# SMD_Latch_Switch_v01.net
KiCad netlist of a schematic drawn in EAGLE
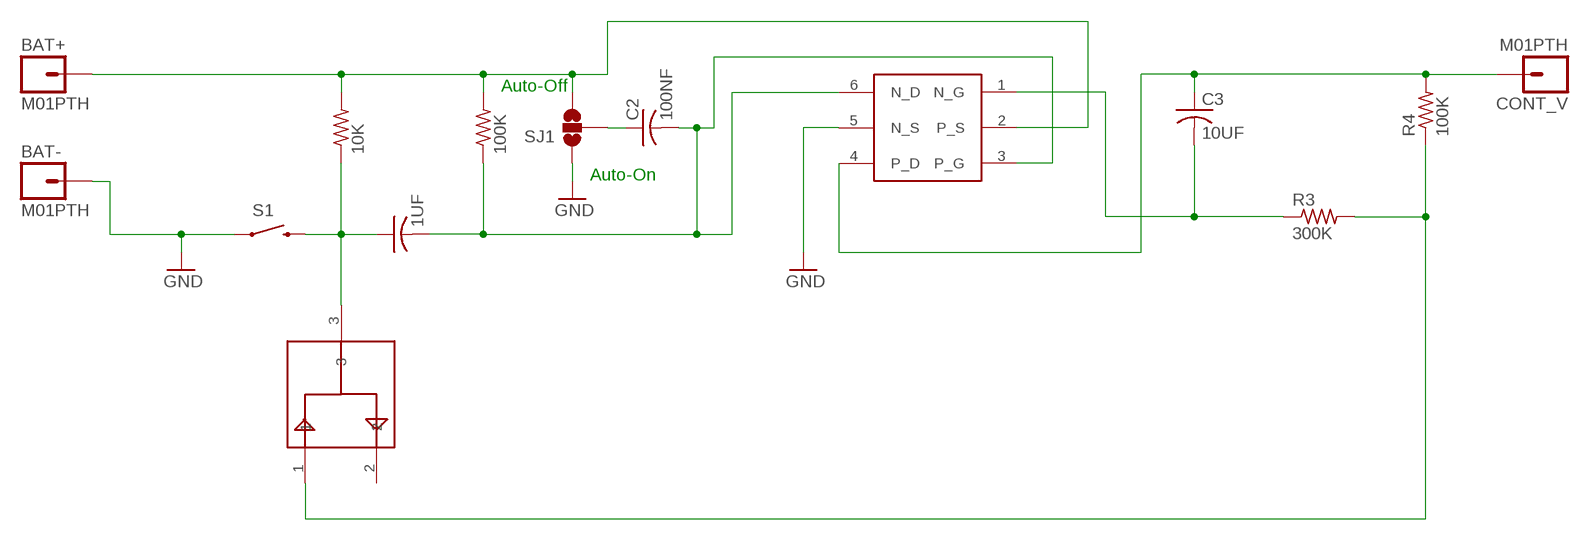
[diagram p0: schematic, sheet 1]

(export (version "E")
  (design (tool "Eeschema 10.0.6"))
  (components
    (comp (ref "1UF")
      (value "1UF")
      (footprint "eagle-import:C0402")
      (libsource (lib "eagle-import") (part "C-USC0402"))
    )
    (comp (ref "10K")
      (value "10K")
      (footprint "eagle-import:R0402")
      (libsource (lib "eagle-import") (part "R-US_R0402"))
    )
    (comp (ref "100K")
      (value "100K")
      (footprint "eagle-import:R0402")
      (libsource (lib "eagle-import") (part "R-US_R0402"))
    )
    (comp (ref "BAT+")
      (value "M01PTH")
      (footprint "eagle-import:1X01")
      (libsource (lib "eagle-import") (part "M01PTH"))
    )
    (comp (ref "BAT-")
      (value "M01PTH")
      (footprint "eagle-import:1X01")
      (libsource (lib "eagle-import") (part "M01PTH"))
    )
    (comp (ref "C2")
      (value "100NF")
      (footprint "eagle-import:C0402")
      (libsource (lib "eagle-import") (part "C-USC0402"))
    )
    (comp (ref "C3")
      (value "10UF")
      (footprint "eagle-import:C0805")
      (libsource (lib "eagle-import") (part "C-USC0805"))
    )
    (comp (ref "CONT_V")
      (value "M01PTH")
      (footprint "eagle-import:1X01")
      (libsource (lib "eagle-import") (part "M01PTH"))
    )
    (comp (ref "R3")
      (value "300K")
      (footprint "eagle-import:R0402")
      (libsource (lib "eagle-import") (part "R-US_R0402"))
    )
    (comp (ref "R4")
      (value "100K")
      (footprint "eagle-import:R0402")
      (libsource (lib "eagle-import") (part "R-US_R0402"))
    )
    (comp (ref "S1")
      (value "SWITCH-MOMENTARY-2SMD")
      (footprint "eagle-import:TACTILE_SWITCH_SMD")
      (libsource (lib "eagle-import") (part "SWITCH-MOMENTARY-2SMD"))
    )
    (comp (ref "SJ1")
      (value "SOLDERJUMPER_2WAYPASTE1&2")
      (footprint "eagle-import:SJ_3_PASTE1&2")
      (libsource (lib "eagle-import") (part "SOLDERJUMPER_2WAYPASTE1&2"))
    )
    (comp (ref "U$1")
      (value "SI3588DV")
      (footprint "eagle-import:SOT23-6")
      (libsource (lib "eagle-import") (part "SI3588DV"))
    )
    (comp (ref "U$2")
      (value "BAV99")
      (footprint "eagle-import:SOT23")
      (libsource (lib "eagle-import") (part "BAV99"))
    )
  )
  (nets
    (net (code "1") (name "GND") (class "Default")
      (node (ref "BAT-") (pin "1") (pinfunction "1_1") (pintype "passive"))
      (node (ref "S1") (pin "1") (pinfunction "1_1") (pintype "passive"))
      (node (ref "SJ1") (pin "1") (pinfunction "1_1") (pintype "passive"))
      (node (ref "U$1") (pin "5") (pinfunction "N_S_5") (pintype "bidirectional"))
    )
    (net (code "2") (name "Net-(C2-Pad1)") (class "Default")
      (node (ref "C2") (pin "1") (pinfunction "1_1") (pintype "passive"))
      (node (ref "SJ1") (pin "2") (pinfunction "2_2") (pintype "passive"))
    )
    (net (code "3") (name "Net-(R3-Pad2)") (class "Default")
      (node (ref "R3") (pin "2") (pinfunction "2_2") (pintype "passive"))
      (node (ref "R4") (pin "1") (pinfunction "1_1") (pintype "passive"))
      (node (ref "U$2") (pin "1") (pinfunction "1_1") (pintype "bidirectional"))
    )
    (net (code "4") (name "Net-(S1-2)") (class "Default")
      (node (ref "10K") (pin "1") (pinfunction "1_1") (pintype "passive"))
      (node (ref "1UF") (pin "1") (pinfunction "1_1") (pintype "passive"))
      (node (ref "S1") (pin "3") (pinfunction "2_3") (pintype "passive"))
      (node (ref "U$2") (pin "3") (pinfunction "3_3") (pintype "bidirectional"))
    )
    (net (code "5") (name "Net-(U$1-N_D)") (class "Default")
      (node (ref "100K") (pin "1") (pinfunction "1_1") (pintype "passive"))
      (node (ref "1UF") (pin "2") (pinfunction "2_2") (pintype "passive"))
      (node (ref "C2") (pin "2") (pinfunction "2_2") (pintype "passive"))
      (node (ref "U$1") (pin "3") (pinfunction "P_G_3") (pintype "bidirectional"))
      (node (ref "U$1") (pin "6") (pinfunction "N_D_6") (pintype "bidirectional"))
    )
    (net (code "6") (name "Net-(U$1-N_G)") (class "Default")
      (node (ref "C3") (pin "2") (pinfunction "2_2") (pintype "passive"))
      (node (ref "R3") (pin "1") (pinfunction "1_1") (pintype "passive"))
      (node (ref "U$1") (pin "1") (pinfunction "N_G_1") (pintype "bidirectional"))
    )
    (net (code "7") (name "Net-(U$1-P_D)") (class "Default")
      (node (ref "C3") (pin "1") (pinfunction "1_1") (pintype "passive"))
      (node (ref "CONT_V") (pin "1") (pinfunction "1_1") (pintype "passive"))
      (node (ref "R4") (pin "2") (pinfunction "2_2") (pintype "passive"))
      (node (ref "U$1") (pin "4") (pinfunction "P_D_4") (pintype "bidirectional"))
    )
    (net (code "8") (name "Net-(U$1-P_S)") (class "Default")
      (node (ref "100K") (pin "2") (pinfunction "2_2") (pintype "passive"))
      (node (ref "10K") (pin "2") (pinfunction "2_2") (pintype "passive"))
      (node (ref "BAT+") (pin "1") (pinfunction "1_1") (pintype "passive"))
      (node (ref "SJ1") (pin "3") (pinfunction "3_3") (pintype "passive"))
      (node (ref "U$1") (pin "2") (pinfunction "P_S_2") (pintype "bidirectional"))
    )
    (net (code "9") (name "unconnected-(U$2-Pad2)") (class "Default")
      (node (ref "U$2") (pin "2") (pinfunction "2_2") (pintype "bidirectional"))
    )
  )
)
